# boost_converter.net
KiCad netlist of a schematic drawn in Altium Designer
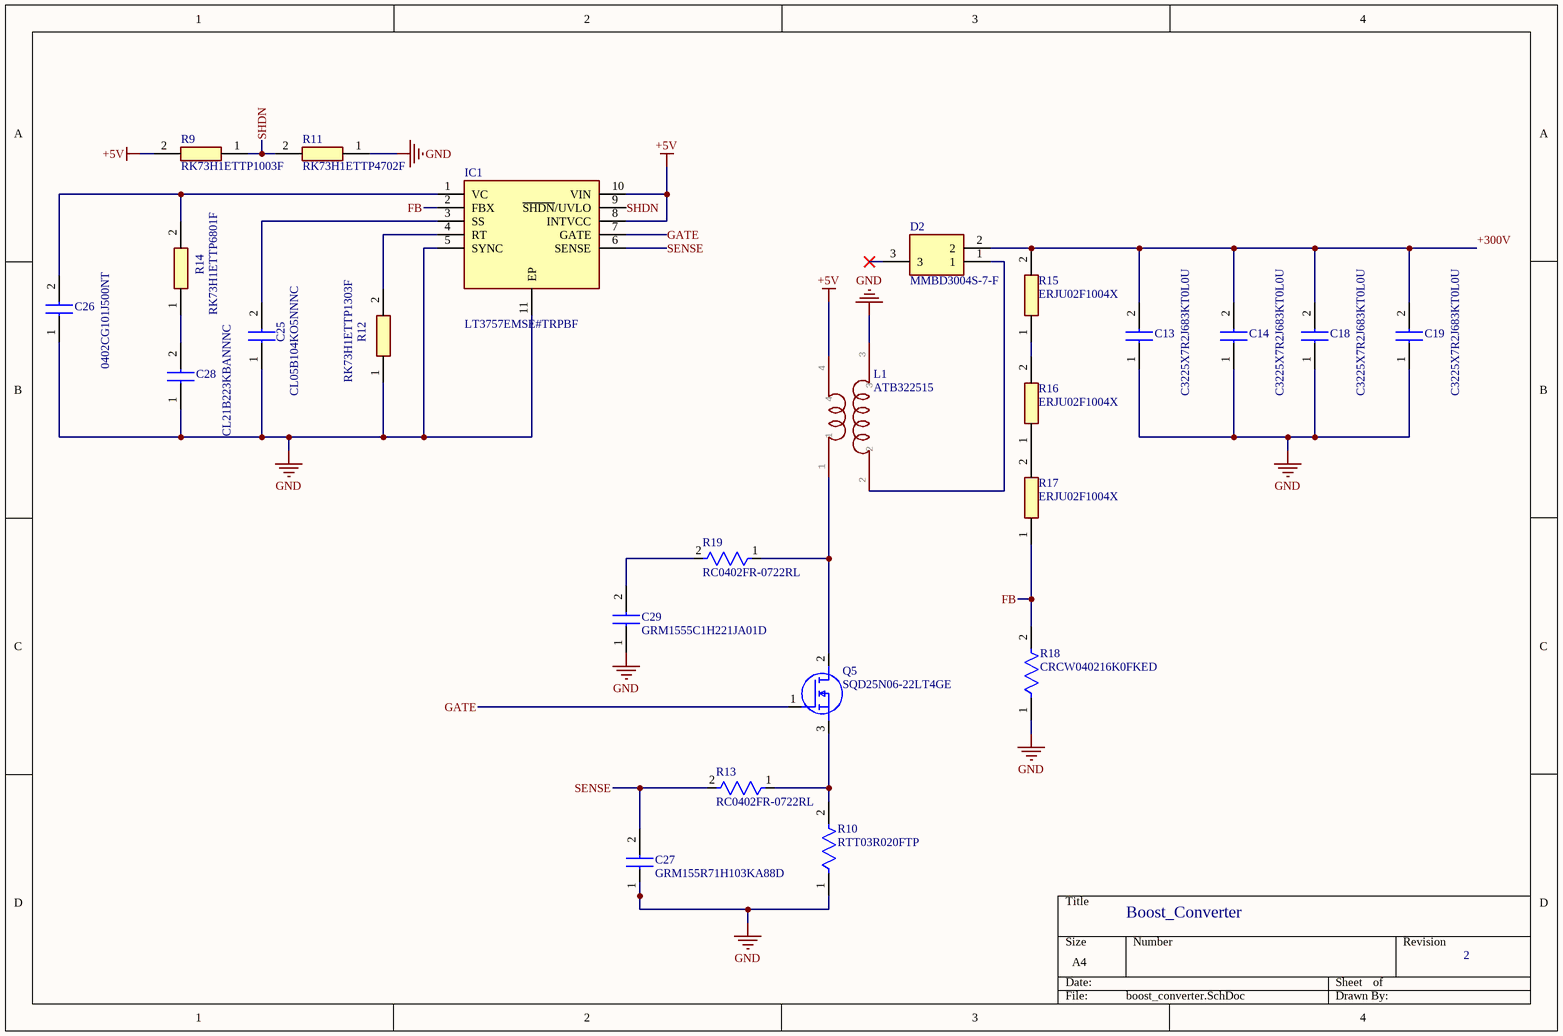
[diagram p0: boost_converter.SchDoc]

(export (version "E")
  (design (tool "Eeschema 10.0.6"))
  (components
    (comp (ref "C13")
      (value "C3225X7R2J683KT0L0U")
      (footprint "SamacSys:CAPC3225X200N")
      (description "Capacitor")
      (fields
        (field (name "MANUFACTURER_PART_NUMBER") "C3225X7R2J683K200AA")
        (field (name "MOUSER PART NUMBER") "810-C3225X7R2J683K")
      )
      (libsource (lib "*") (part "C3225X7R2J683K200AA"))
    )
    (comp (ref "C14")
      (value "C3225X7R2J683KT0L0U")
      (footprint "SamacSys:CAPC3225X200N")
      (description "Capacitor")
      (fields
        (field (name "MANUFACTURER_PART_NUMBER") "C3225X7R2J683K200AA")
        (field (name "MOUSER PART NUMBER") "810-C3225X7R2J683K")
      )
      (libsource (lib "*") (part "C3225X7R2J683K200AA"))
    )
    (comp (ref "C18")
      (value "C3225X7R2J683KT0L0U")
      (footprint "SamacSys:CAPC3225X200N")
      (description "Capacitor")
      (fields
        (field (name "MANUFACTURER_PART_NUMBER") "C3225X7R2J683K200AA")
        (field (name "MOUSER PART NUMBER") "810-C3225X7R2J683K")
      )
      (libsource (lib "*") (part "C3225X7R2J683K200AA"))
    )
    (comp (ref "C19")
      (value "C3225X7R2J683KT0L0U")
      (footprint "SamacSys:CAPC3225X200N")
      (description "Capacitor")
      (fields
        (field (name "MANUFACTURER_PART_NUMBER") "C3225X7R2J683K200AA")
        (field (name "MOUSER PART NUMBER") "810-C3225X7R2J683K")
      )
      (libsource (lib "*") (part "C3225X7R2J683K200AA"))
    )
    (comp (ref "C25")
      (value "CL05B104KO5NNNC")
      (footprint "SamacSys:CAPC1005X55N")
      (description "Capacitor")
      (fields (field (name "MOUSER PART NUMBER") "187-CL05B104KO5NNNC"))
      (libsource (lib "*") (part "CL05B104KO5NNNC"))
    )
    (comp (ref "C26")
      (value "0402CG101J500NT")
      (footprint "SamacSys:CAPC1005X55N")
      (description "Capacitor")
      (libsource (lib "*") (part "0402CG101J500NT"))
    )
    (comp (ref "C27")
      (value "GRM155R71H103KA88D")
      (footprint "SamacSys:GRM15x")
      (description "Capacitor")
      (fields (field (name "MOUSER PART NUMBER") "81-GRM155R71H103KA8D"))
      (libsource (lib "*") (part "GRM155R71H103KA88D"))
    )
    (comp (ref "C28")
      (value "CL21B223KBANNNC")
      (footprint "SamacSys:CAPC2012X75N")
      (description "Capacitor")
      (fields (field (name "MOUSER PART NUMBER") "187-CL21B223KBANNNC"))
      (libsource (lib "*") (part "CL21B223KBANNNC"))
    )
    (comp (ref "C29")
      (value "GRM1555C1H221JA01D")
      (footprint "SamacSys:CAPC1005X70N")
      (description "Capacitor")
      (fields (field (name "MOUSER PART NUMBER") "81-GRM1555C1H221JA01"))
      (libsource (lib "*") (part "GRM1555C1H221JA01D"))
    )
    (comp (ref "D2")
      (value "MMBD3004S-7-F")
      (footprint "SamacSys:SOT96P240X100-3N")
      (description "Diode")
      (fields (field (name "MOUSER PART NUMBER") "621-MMBD3004S-F"))
      (libsource (lib "*") (part "MMBD3004S-7-F"))
    )
    (comp (ref "IC1")
      (value "LT3757EMSE#TRPBF")
      (footprint "SamacSys:SOP50P490X110-11N")
      (description "Integrated Circuit")
      (fields (field (name "MANUFACTURER_PART_NUMBER") "LT3757EMSETRPBF"))
      (libsource (lib "*") (part "LT3757EMSETRPBF"))
    )
    (comp (ref "L1")
      (value "ATB322515")
      (footprint "ATB322515")
      (libsource (lib "ATB322515") (part "ATB322515"))
    )
    (comp (ref "Q5")
      (value "SQD25N06-22LT4GE")
      (footprint "SamacSys:IPD25N06S4L30ATMA2")
      (description "60V 25A 30mΩ@10V 2.5V 1PCSNChannel TO252-2L MOSFETs ROHS")
      (fields
        (field (name "MANUFACTURER_PART_NUMBER") "25N06")
        (field (name "MOUSER PART NUMBER") "IPD25N06S4L30ATMA2")
      )
      (libsource (lib "*") (part "IPD25N06S4L30ATMA2"))
    )
    (comp (ref "R9")
      (value "RK73H1ETTP1003F")
      (footprint "SamacSys:RESC1005X40N")
      (description "Resistor")
      (fields (field (name "MOUSER PART NUMBER") "660-RK73H1ETTP1003F"))
      (libsource (lib "*") (part "RK73H1ETTP1003F"))
    )
    (comp (ref "R10")
      (value "RTT03R020FTP")
      (footprint "FP-PA0402-MFG")
      (description "METAL CURRENT SENSOR 0402 1% 150")
      (fields (field (name "MANUFACTURER") "Yageo") (field (name "TOLERANCE") "1%"))
      (libsource (lib "Altium Content Vault") (part "1029c3af85768c4190bb7ad29bc67b5"))
    )
    (comp (ref "R11")
      (value "RK73H1ETTP4702F")
      (footprint "SamacSys:RESC1005X40N")
      (description "Resistor")
      (fields (field (name "MOUSER PART NUMBER") "660-RK73H1ETTP4702F"))
      (libsource (lib "*") (part "RK73H1ETTP4702F"))
    )
    (comp (ref "R12")
      (value "RK73H1ETTP1303F")
      (footprint "SamacSys:RESC1005X40N")
      (description "Resistor")
      (fields (field (name "MOUSER PART NUMBER") "660-RK73H1ETTP1303F"))
      (libsource (lib "*") (part "RK73H1ETTP1303F"))
    )
    (comp (ref "R13")
      (value "RC0402FR-0722RL")
      (footprint "FP-RC0402-0_4-MFG")
      (fields (field (name "TOLERANCE") "1%"))
      (libsource (lib "Altium Content Vault") (part "RC0402FR-0722RL"))
    )
    (comp (ref "R14")
      (value "RK73H1ETTP6801F")
      (footprint "SamacSys:RESC1005X40N")
      (description "Resistor")
      (fields (field (name "MOUSER PART NUMBER") "660-RK73H1ETTP6801F"))
      (libsource (lib "*") (part "RK73H1ETTP6801F"))
    )
    (comp (ref "R15")
      (value "ERJU02F1004X")
      (footprint "SamacSys:ERJS02_U02_(0402)")
      (description "Resistor")
      (libsource (lib "*") (part "ERJU02F1004X"))
    )
    (comp (ref "R16")
      (value "ERJU02F1004X")
      (footprint "SamacSys:ERJS02_U02_(0402)")
      (description "Resistor")
      (libsource (lib "*") (part "ERJU02F1004X"))
    )
    (comp (ref "R17")
      (value "ERJU02F1004X")
      (footprint "SamacSys:ERJS02_U02_(0402)")
      (description "Resistor")
      (libsource (lib "*") (part "ERJU02F1004X"))
    )
    (comp (ref "R18")
      (value "CRCW040216K0FKED")
      (footprint "FP-CRCW0402-e3-IPC_C")
      (description "RES Thick Film, 16kΩ, 1%, 0.063W, 100ppm/°C, 0402")
      (fields (field (name "TOLERANCE") "1%"))
      (libsource (lib "Altium Content Vault") (part "1029c3af85768c4190bb7ad29bc67b5"))
    )
    (comp (ref "R19")
      (value "RC0402FR-0722RL")
      (footprint "FP-RC0402-0_4-MFG")
      (fields (field (name "TOLERANCE") "1%"))
      (libsource (lib "Altium Content Vault") (part "RC0402FR-0722RL"))
    )
  )
  (nets
    (net (code "1") (name "+5V") (class "Default")
      (node (ref "IC1") (pin "10") (pinfunction "VIN_10") (pintype "passive"))
      (node (ref "IC1") (pin "8") (pinfunction "INTVCC_8") (pintype "passive"))
      (node (ref "L1") (pin "4") (pinfunction "4_4") (pintype "passive"))
      (node (ref "R9") (pin "2") (pinfunction "2_2") (pintype "passive"))
    )
    (net (code "2") (name "/+300V") (class "Default")
      (node (ref "C13") (pin "2") (pinfunction "2_2") (pintype "passive"))
      (node (ref "C14") (pin "2") (pinfunction "2_2") (pintype "passive"))
      (node (ref "C18") (pin "2") (pinfunction "2_2") (pintype "passive"))
      (node (ref "C19") (pin "2") (pinfunction "2_2") (pintype "passive"))
      (node (ref "D2") (pin "2") (pinfunction "2_2") (pintype "passive"))
      (node (ref "R15") (pin "2") (pinfunction "2_2") (pintype "passive"))
    )
    (net (code "3") (name "/FB") (class "Default")
      (node (ref "IC1") (pin "2") (pinfunction "FBX_2") (pintype "passive"))
      (node (ref "R17") (pin "1") (pinfunction "1_1") (pintype "passive"))
      (node (ref "R18") (pin "2") (pinfunction "2_2") (pintype "passive"))
    )
    (net (code "4") (name "/GATE") (class "Default")
      (node (ref "IC1") (pin "7") (pinfunction "GATE_7") (pintype "passive"))
      (node (ref "Q5") (pin "1") (pinfunction "G_1") (pintype "passive"))
    )
    (net (code "5") (name "/SENSE") (class "Default")
      (node (ref "C27") (pin "2") (pinfunction "2_2") (pintype "passive"))
      (node (ref "IC1") (pin "6") (pinfunction "SENSE_6") (pintype "passive"))
      (node (ref "R13") (pin "2") (pinfunction "2_2") (pintype "passive"))
    )
    (net (code "6") (name "/SHDN") (class "Default")
      (node (ref "IC1") (pin "9") (pinfunction "~{SHDN}/UVLO_9") (pintype "passive"))
      (node (ref "R11") (pin "2") (pinfunction "2_2") (pintype "passive"))
      (node (ref "R9") (pin "1") (pinfunction "1_1") (pintype "passive"))
    )
    (net (code "7") (name "GND") (class "Default")
      (node (ref "C13") (pin "1") (pinfunction "1_1") (pintype "passive"))
      (node (ref "C14") (pin "1") (pinfunction "1_1") (pintype "passive"))
      (node (ref "C18") (pin "1") (pinfunction "1_1") (pintype "passive"))
      (node (ref "C19") (pin "1") (pinfunction "1_1") (pintype "passive"))
      (node (ref "C25") (pin "1") (pinfunction "1_1") (pintype "passive"))
      (node (ref "C26") (pin "1") (pinfunction "1_1") (pintype "passive"))
      (node (ref "C27") (pin "1") (pinfunction "1_1") (pintype "passive"))
      (node (ref "C28") (pin "1") (pinfunction "1_1") (pintype "passive"))
      (node (ref "C29") (pin "1") (pinfunction "1_1") (pintype "passive"))
      (node (ref "IC1") (pin "11") (pinfunction "EP_11") (pintype "passive"))
      (node (ref "IC1") (pin "5") (pinfunction "SYNC_5") (pintype "passive"))
      (node (ref "L1") (pin "3") (pinfunction "3_3") (pintype "passive"))
      (node (ref "R10") (pin "1") (pinfunction "1_1") (pintype "passive"))
      (node (ref "R11") (pin "1") (pinfunction "1_1") (pintype "passive"))
      (node (ref "R12") (pin "1") (pinfunction "1_1") (pintype "passive"))
      (node (ref "R18") (pin "1") (pinfunction "1_1") (pintype "passive"))
    )
    (net (code "8") (name "Net-(C28-Pad2)") (class "Default")
      (node (ref "C28") (pin "2") (pinfunction "2_2") (pintype "passive"))
      (node (ref "R14") (pin "1") (pinfunction "1_1") (pintype "passive"))
    )
    (net (code "9") (name "Net-(C29-Pad2)") (class "Default")
      (node (ref "C29") (pin "2") (pinfunction "2_2") (pintype "passive"))
      (node (ref "R19") (pin "2") (pinfunction "2_2") (pintype "passive"))
    )
    (net (code "10") (name "Net-(D2-Pad1)") (class "Default")
      (node (ref "D2") (pin "1") (pinfunction "1_1") (pintype "passive"))
      (node (ref "L1") (pin "2") (pinfunction "2_2") (pintype "passive"))
    )
    (net (code "11") (name "Net-(IC1-RT)") (class "Default")
      (node (ref "IC1") (pin "4") (pinfunction "RT_4") (pintype "passive"))
      (node (ref "R12") (pin "2") (pinfunction "2_2") (pintype "passive"))
    )
    (net (code "12") (name "Net-(IC1-SS)") (class "Default")
      (node (ref "C25") (pin "2") (pinfunction "2_2") (pintype "passive"))
      (node (ref "IC1") (pin "3") (pinfunction "SS_3") (pintype "passive"))
    )
    (net (code "13") (name "Net-(IC1-VC)") (class "Default")
      (node (ref "C26") (pin "2") (pinfunction "2_2") (pintype "passive"))
      (node (ref "IC1") (pin "1") (pinfunction "VC_1") (pintype "passive"))
      (node (ref "R14") (pin "2") (pinfunction "2_2") (pintype "passive"))
    )
    (net (code "14") (name "Net-(Q5-D)") (class "Default")
      (node (ref "L1") (pin "1") (pinfunction "1_1") (pintype "passive"))
      (node (ref "Q5") (pin "2") (pinfunction "D_2") (pintype "passive"))
      (node (ref "R19") (pin "1") (pinfunction "1_1") (pintype "passive"))
    )
    (net (code "15") (name "Net-(Q5-S)") (class "Default")
      (node (ref "Q5") (pin "3") (pinfunction "S_3") (pintype "passive"))
      (node (ref "R10") (pin "2") (pinfunction "2_2") (pintype "passive"))
      (node (ref "R13") (pin "1") (pinfunction "1_1") (pintype "passive"))
    )
    (net (code "16") (name "Net-(R15-Pad1)") (class "Default")
      (node (ref "R15") (pin "1") (pinfunction "1_1") (pintype "passive"))
      (node (ref "R16") (pin "2") (pinfunction "2_2") (pintype "passive"))
    )
    (net (code "17") (name "Net-(R16-Pad1)") (class "Default")
      (node (ref "R16") (pin "1") (pinfunction "1_1") (pintype "passive"))
      (node (ref "R17") (pin "2") (pinfunction "2_2") (pintype "passive"))
    )
    (net (code "18") (name "unconnected-(D2-Pad3)") (class "Default")
      (node (ref "D2") (pin "3") (pinfunction "3_3") (pintype "passive+no_connect"))
    )
  )
)
